# converter.net
KiCad netlist of a schematic drawn in Altium Designer
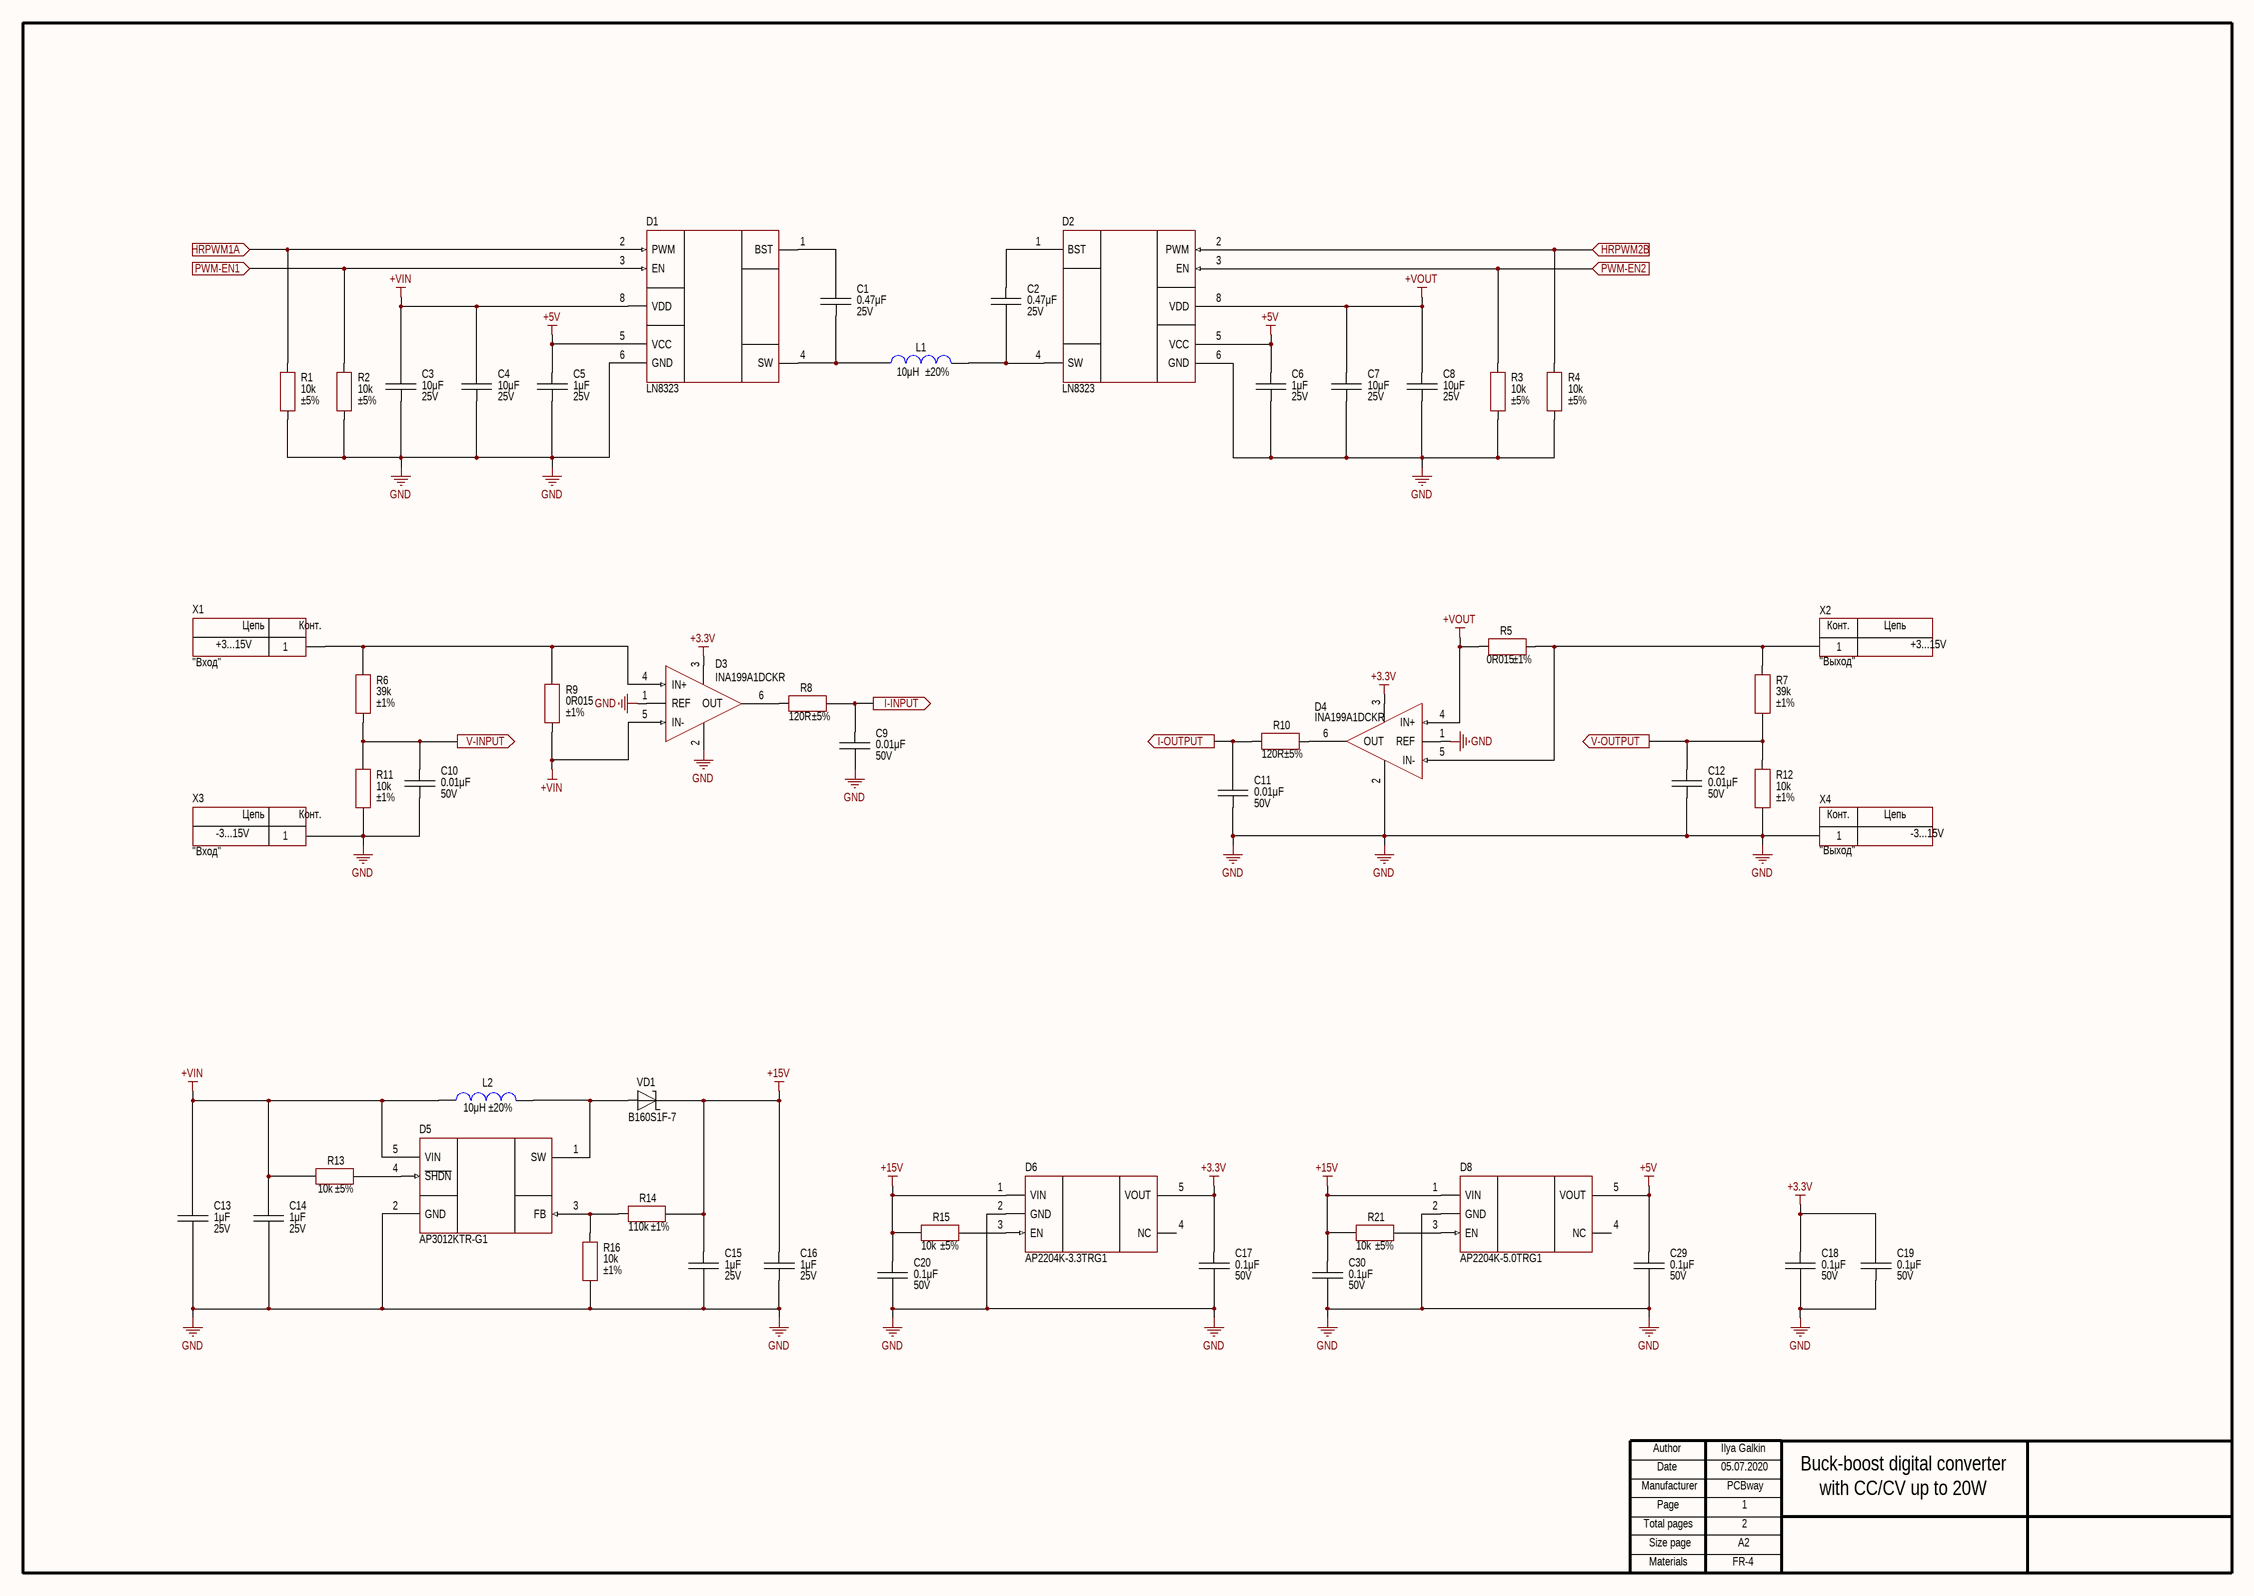
[diagram p0: converter.SchDoc]

(export (version "E")
  (design (tool "Eeschema 10.0.6"))
  (components
    (comp (ref "C1")
      (value "0.47μF")
      (footprint "CAP: 0805")
      (fields
        (field (name "MANUFACTURER") "Samsung")
        (field (name "PARTNUMBER") "CL21B474KAFNNNG")
        (field (name "VALUEMANUFACTURERPARTNUMBER") "Ceramic capacitor, 0.47μF, X7R, ±10%, 25V, 0805, -55...+125°C")
        (field (name "VOLTAGE") "25V")
      )
      (libsource (lib "Capacitor") (part "Ceramic_0805"))
    )
    (comp (ref "C2")
      (value "0.47μF")
      (footprint "CAP: 0805")
      (fields
        (field (name "MANUFACTURER") "Samsung")
        (field (name "PARTNUMBER") "CL21B474KAFNNNG")
        (field (name "VALUEMANUFACTURERPARTNUMBER") "Ceramic capacitor, 0.47μF, X7R, ±10%, 25V, 0805, -55...+125°C")
        (field (name "VOLTAGE") "25V")
      )
      (libsource (lib "Capacitor") (part "Ceramic_0805"))
    )
    (comp (ref "C3")
      (value "10μF")
      (footprint "CAP: 1210")
      (fields
        (field (name "MANUFACTURER") "Samsung")
        (field (name "PARTNUMBER") "CL32B106KAJNNNE")
        (field (name "VALUEMANUFACTURERPARTNUMBER") "Ceramic capacitor, 10μF, X7R, ±10%, 25V, 1210, -55...+125°C")
        (field (name "VOLTAGE") "25V")
      )
      (libsource (lib "Capacitor") (part "Ceramic_1210"))
    )
    (comp (ref "C4")
      (value "10μF")
      (footprint "CAP: 1210")
      (fields
        (field (name "MANUFACTURER") "Samsung")
        (field (name "PARTNUMBER") "CL32B106KAJNNNE")
        (field (name "VALUEMANUFACTURERPARTNUMBER") "Ceramic capacitor, 10μF, X7R, ±10%, 25V, 1210, -55...+125°C")
        (field (name "VOLTAGE") "25V")
      )
      (libsource (lib "Capacitor") (part "Ceramic_1210"))
    )
    (comp (ref "C5")
      (value "1μF")
      (footprint "CAP: 0603")
      (fields
        (field (name "MANUFACTURER") "Samsung")
        (field (name "PARTNUMBER") "CL10B105KA8NNNC")
        (field (name "VALUEMANUFACTURERPARTNUMBER") "Ceramic capacitor, 1μF, X7R, ±10%, 25V, 0603, -55...+125°C")
        (field (name "VOLTAGE") "25V")
      )
      (libsource (lib "Capacitor") (part "Ceramic_0603"))
    )
    (comp (ref "C6")
      (value "1μF")
      (footprint "CAP: 0603")
      (fields
        (field (name "MANUFACTURER") "Samsung")
        (field (name "PARTNUMBER") "CL10B105KA8NNNC")
        (field (name "VALUEMANUFACTURERPARTNUMBER") "Ceramic capacitor, 1μF, X7R, ±10%, 25V, 0603, -55...+125°C")
        (field (name "VOLTAGE") "25V")
      )
      (libsource (lib "Capacitor") (part "Ceramic_0603"))
    )
    (comp (ref "C7")
      (value "10μF")
      (footprint "CAP: 1210")
      (fields
        (field (name "MANUFACTURER") "Samsung")
        (field (name "PARTNUMBER") "CL32B106KAJNNNE")
        (field (name "VALUEMANUFACTURERPARTNUMBER") "Ceramic capacitor, 10μF, X7R, ±10%, 25V, 1210, -55...+125°C")
        (field (name "VOLTAGE") "25V")
      )
      (libsource (lib "Capacitor") (part "Ceramic_1210"))
    )
    (comp (ref "C8")
      (value "10μF")
      (footprint "CAP: 1210")
      (fields
        (field (name "MANUFACTURER") "Samsung")
        (field (name "PARTNUMBER") "CL32B106KAJNNNE")
        (field (name "VALUEMANUFACTURERPARTNUMBER") "Ceramic capacitor, 10μF, X7R, ±10%, 25V, 1210, -55...+125°C")
        (field (name "VOLTAGE") "25V")
      )
      (libsource (lib "Capacitor") (part "Ceramic_1210"))
    )
    (comp (ref "C9")
      (value "0.01μF")
      (footprint "CAP: 0603")
      (fields
        (field (name "MANUFACTURER") "Yageo")
        (field (name "PARTNUMBER") "CL10B103KB8NNNC")
        (field (name "VALUEMANUFACTURERPARTNUMBER") "Ceramic capacitor, 0.01μF, X7R, ±10%, 50V, 0603, -55...+125°C")
        (field (name "VOLTAGE") "50V")
      )
      (libsource (lib "Capacitor") (part "Ceramic_0603"))
    )
    (comp (ref "C10")
      (value "0.01μF")
      (footprint "CAP: 0603")
      (fields
        (field (name "MANUFACTURER") "Yageo")
        (field (name "PARTNUMBER") "CL10B103KB8NNNC")
        (field (name "VALUEMANUFACTURERPARTNUMBER") "Ceramic capacitor, 0.01μF, X7R, ±10%, 50V, 0603, -55...+125°C")
        (field (name "VOLTAGE") "50V")
      )
      (libsource (lib "Capacitor") (part "Ceramic_0603"))
    )
    (comp (ref "C11")
      (value "0.01μF")
      (footprint "CAP: 0603")
      (fields
        (field (name "MANUFACTURER") "Yageo")
        (field (name "PARTNUMBER") "CL10B103KB8NNNC")
        (field (name "VALUEMANUFACTURERPARTNUMBER") "Ceramic capacitor, 0.01μF, X7R, ±10%, 50V, 0603, -55...+125°C")
        (field (name "VOLTAGE") "50V")
      )
      (libsource (lib "Capacitor") (part "Ceramic_0603"))
    )
    (comp (ref "C12")
      (value "0.01μF")
      (footprint "CAP: 0603")
      (fields
        (field (name "MANUFACTURER") "Yageo")
        (field (name "PARTNUMBER") "CL10B103KB8NNNC")
        (field (name "VALUEMANUFACTURERPARTNUMBER") "Ceramic capacitor, 0.01μF, X7R, ±10%, 50V, 0603, -55...+125°C")
        (field (name "VOLTAGE") "50V")
      )
      (libsource (lib "Capacitor") (part "Ceramic_0603"))
    )
    (comp (ref "C13")
      (value "1μF")
      (footprint "CAP: 0603")
      (fields
        (field (name "MANUFACTURER") "Samsung")
        (field (name "PARTNUMBER") "CL10B105KA8NNNC")
        (field (name "VALUEMANUFACTURERPARTNUMBER") "Ceramic capacitor, 1μF, X7R, ±10%, 25V, 0603, -55...+125°C")
        (field (name "VOLTAGE") "25V")
      )
      (libsource (lib "Capacitor") (part "Ceramic_0603"))
    )
    (comp (ref "C14")
      (value "1μF")
      (footprint "CAP: 0603")
      (fields
        (field (name "MANUFACTURER") "Samsung")
        (field (name "PARTNUMBER") "CL10B105KA8NNNC")
        (field (name "VALUEMANUFACTURERPARTNUMBER") "Ceramic capacitor, 1μF, X7R, ±10%, 25V, 0603, -55...+125°C")
        (field (name "VOLTAGE") "25V")
      )
      (libsource (lib "Capacitor") (part "Ceramic_0603"))
    )
    (comp (ref "C15")
      (value "1μF")
      (footprint "CAP: 0603")
      (fields
        (field (name "MANUFACTURER") "Samsung")
        (field (name "PARTNUMBER") "CL10B105KA8NNNC")
        (field (name "VALUEMANUFACTURERPARTNUMBER") "Ceramic capacitor, 1μF, X7R, ±10%, 25V, 0603, -55...+125°C")
        (field (name "VOLTAGE") "25V")
      )
      (libsource (lib "Capacitor") (part "Ceramic_0603"))
    )
    (comp (ref "C16")
      (value "1μF")
      (footprint "CAP: 0603")
      (fields
        (field (name "MANUFACTURER") "Samsung")
        (field (name "PARTNUMBER") "CL10B105KA8NNNC")
        (field (name "VALUEMANUFACTURERPARTNUMBER") "Ceramic capacitor, 1μF, X7R, ±10%, 25V, 0603, -55...+125°C")
        (field (name "VOLTAGE") "25V")
      )
      (libsource (lib "Capacitor") (part "Ceramic_0603"))
    )
    (comp (ref "C17")
      (value "0.1μF")
      (footprint "CAP: 0603")
      (fields
        (field (name "MANUFACTURER") "Yageo")
        (field (name "PARTNUMBER") "CL10B104KB8WPND")
        (field (name "VALUEMANUFACTURERPARTNUMBER") "Ceramic capacitor, 0.1μF, X7R, ±10%, 50V, 0603, -55...+125°C")
        (field (name "VOLTAGE") "50V")
      )
      (libsource (lib "Capacitor") (part "Ceramic_0603"))
    )
    (comp (ref "C18")
      (value "0.1μF")
      (footprint "CAP: 0603")
      (fields
        (field (name "MANUFACTURER") "Yageo")
        (field (name "PARTNUMBER") "CL10B104KB8WPND")
        (field (name "VALUEMANUFACTURERPARTNUMBER") "Ceramic capacitor, 0.1μF, X7R, ±10%, 50V, 0603, -55...+125°C")
        (field (name "VOLTAGE") "50V")
      )
      (libsource (lib "Capacitor") (part "Ceramic_0603"))
    )
    (comp (ref "C19")
      (value "0.1μF")
      (footprint "CAP: 0603")
      (fields
        (field (name "MANUFACTURER") "Yageo")
        (field (name "PARTNUMBER") "CL10B104KB8WPND")
        (field (name "VALUEMANUFACTURERPARTNUMBER") "Ceramic capacitor, 0.1μF, X7R, ±10%, 50V, 0603, -55...+125°C")
        (field (name "VOLTAGE") "50V")
      )
      (libsource (lib "Capacitor") (part "Ceramic_0603"))
    )
    (comp (ref "C20")
      (value "0.1μF")
      (footprint "CAP: 0603")
      (fields
        (field (name "MANUFACTURER") "Yageo")
        (field (name "PARTNUMBER") "CL10B104KB8WPND")
        (field (name "VALUEMANUFACTURERPARTNUMBER") "Ceramic capacitor, 0.1μF, X7R, ±10%, 50V, 0603, -55...+125°C")
        (field (name "VOLTAGE") "50V")
      )
      (libsource (lib "Capacitor") (part "Ceramic_0603"))
    )
    (comp (ref "C29")
      (value "0.1μF")
      (footprint "CAP: 0603")
      (fields
        (field (name "MANUFACTURER") "Yageo")
        (field (name "PARTNUMBER") "CL10B104KB8WPND")
        (field (name "VALUEMANUFACTURERPARTNUMBER") "Ceramic capacitor, 0.1μF, X7R, ±10%, 50V, 0603, -55...+125°C")
        (field (name "VOLTAGE") "50V")
      )
      (libsource (lib "Capacitor") (part "Ceramic_0603"))
    )
    (comp (ref "C30")
      (value "0.1μF")
      (footprint "CAP: 0603")
      (fields
        (field (name "MANUFACTURER") "Yageo")
        (field (name "PARTNUMBER") "CL10B104KB8WPND")
        (field (name "VALUEMANUFACTURERPARTNUMBER") "Ceramic capacitor, 0.1μF, X7R, ±10%, 50V, 0603, -55...+125°C")
        (field (name "VOLTAGE") "50V")
      )
      (libsource (lib "Capacitor") (part "Ceramic_0603"))
    )
    (comp (ref "D1")
      (value "~")
      (footprint "8-SOIC-PAD")
      (description "Gate driver")
      (fields
        (field (name "MANUFACTURER") "Chipown")
        (field (name "VALUEMANUFACTURERPARTNUMBER") "Half-bridge module, 2N channel, 100kHz, 6A, supply 4...30V, -40...+125°C, 8-SOIC-PAD")
        (field (name "PARTNUMBER") "LN8323")
      )
      (libsource (lib "") (part "LN8323_1"))
    )
    (comp (ref "D2")
      (value "~")
      (footprint "8-SOIC-PAD")
      (description "Gate driver")
      (fields
        (field (name "MANUFACTURER") "Chipown")
        (field (name "VALUEMANUFACTURERPARTNUMBER") "Half-bridge module, 2N channel, 100kHz, 6A, supply 4...30V, -40...+125°C, 8-SOIC-PAD")
        (field (name "PARTNUMBER") "LN8323")
      )
      (libsource (lib "IC. Gate driver") (part "LN8323"))
    )
    (comp (ref "D3")
      (value "~")
      (footprint "SC70-6")
      (description "Current monitor")
      (fields
        (field (name "MANUFACTURER") "Texas Instruments")
        (field (name "VALUEMANUFACTURERPARTNUMBER") "IC current monitor, ±1.5%, 50V/V, -0.3...+26V, -40...+125°C, SOT23-5")
        (field (name "PARTNUMBER") "INA199A1DCKR")
      )
      (libsource (lib "IC. Sensor") (part "INA199A1DCKR"))
    )
    (comp (ref "D4")
      (value "~")
      (footprint "SC70-6")
      (description "Current monitor")
      (fields
        (field (name "MANUFACTURER") "Texas Instruments")
        (field (name "VALUEMANUFACTURERPARTNUMBER") "IC current monitor, ±1.5%, 50V/V, -0.3...+26V, -40...+125°C, SOT23-5")
        (field (name "PARTNUMBER") "INA199A1DCKR")
      )
      (libsource (lib "IC. Sensor") (part "INA199A1DCKR"))
    )
    (comp (ref "D5")
      (value "~")
      (footprint "SOT23-5")
      (description "Boost converter")
      (fields
        (field (name "MANUFACTURER") "Diodes Incorporated")
        (field (name "VALUEMANUFACTURERPARTNUMBER") "DC/DC boost converter, input 2.6...16V, 1.5MHz, output 3...29V, 0.5A, -40...+85°C, SOT23-5")
        (field (name "PARTNUMBER") "AP3012KTR-G1")
      )
      (libsource (lib "IC. Power supply") (part "AP3012KTR-G1"))
    )
    (comp (ref "D6")
      (value "~")
      (footprint "SOT23-5")
      (description "Linear voltage regulator")
      (fields
        (field (name "MANUFACTURER") "Diodes Incorporated")
        (field (name "VALUEMANUFACTURERPARTNUMBER") "Linear voltage regulator, input 4...24V, 0.5V, output 3.3V, 0.15A, -40...+85°C, SOT23-6")
        (field (name "PARTNUMBER") "AP2204K-3.3TRG1")
      )
      (libsource (lib "IC. Power supply") (part "AP2204K-3.3TRG1"))
    )
    (comp (ref "D8")
      (value "~")
      (footprint "SOT23-5")
      (description "Linear voltage regulator")
      (fields
        (field (name "MANUFACTURER") "Diodes Incorporated")
        (field (name "VALUEMANUFACTURERPARTNUMBER") "Linear voltage regulator, input 4...24V, 0.5V, output 5V, 0.15A, -40...+85°C, SOT23-6")
        (field (name "PARTNUMBER") "AP2204K-5.0TRG1")
      )
      (libsource (lib "IC. Power supply") (part "AP2204K-3.3TRG1"))
    )
    (comp (ref "L1")
      (value "10μH")
      (footprint "IND: SDR1006")
      (fields
        (field (name "MANUFACTURER") "Bourns")
        (field (name "PARTNUMBER") "SDR1006-100ML")
        (field (name "VALUEMANUFACTURERPARTNUMBER") "Fixed inductor, 10μH, ±20%, SDR0805, 2.6A, -40...+125°C")
        (field (name "TOLERANCE") "±20%")
      )
      (libsource (lib "Inductor") (part "Inductor_SDR1006"))
    )
    (comp (ref "L2")
      (value "10μH")
      (footprint "IND: SDR0403")
      (fields
        (field (name "MANUFACTURER") "Bourns")
        (field (name "PARTNUMBER") "SDR0403-100ML")
        (field (name "VALUEMANUFACTURERPARTNUMBER") "Fixed inductor, 10μH, ±20%, SDR0403, 1.15A, -40...+125°C")
        (field (name "TOLERANCE") "±20%")
      )
      (libsource (lib "Inductor") (part "Inductor_SDR0403"))
    )
    (comp (ref "R1")
      (value "10k")
      (footprint "RES: 0603")
      (fields
        (field (name "MANUFACTURER") "Yageo")
        (field (name "PARTNUMBER") "RC0603JR-0710KL")
        (field (name "VALUEMANUFACTURERPARTNUMBER") "Resistor film, 10k, ±5%, 0603, 0.1W, -55...+125°C")
        (field (name "TOLERANCE") "±5%")
      )
      (libsource (lib "Resistor") (part "Resistor_0603"))
    )
    (comp (ref "R2")
      (value "10k")
      (footprint "RES: 0603")
      (fields
        (field (name "MANUFACTURER") "Yageo")
        (field (name "PARTNUMBER") "RC0603JR-0710KL")
        (field (name "VALUEMANUFACTURERPARTNUMBER") "Resistor film, 10k, ±5%, 0603, 0.1W, -55...+125°C")
        (field (name "TOLERANCE") "±5%")
      )
      (libsource (lib "Resistor") (part "Resistor_0603"))
    )
    (comp (ref "R3")
      (value "10k")
      (footprint "RES: 0603")
      (fields
        (field (name "MANUFACTURER") "Yageo")
        (field (name "PARTNUMBER") "RC0603JR-0710KL")
        (field (name "VALUEMANUFACTURERPARTNUMBER") "Resistor film, 10k, ±5%, 0603, 0.1W, -55...+125°C")
        (field (name "TOLERANCE") "±5%")
      )
      (libsource (lib "Resistor") (part "Resistor_0603"))
    )
    (comp (ref "R4")
      (value "10k")
      (footprint "RES: 0603")
      (fields
        (field (name "MANUFACTURER") "Yageo")
        (field (name "PARTNUMBER") "RC0603JR-0710KL")
        (field (name "VALUEMANUFACTURERPARTNUMBER") "Resistor film, 10k, ±5%, 0603, 0.1W, -55...+125°C")
        (field (name "TOLERANCE") "±5%")
      )
      (libsource (lib "Resistor") (part "Resistor_0603"))
    )
    (comp (ref "R5")
      (value "0R015")
      (footprint "RES: CSS2H (2512)")
      (fields
        (field (name "MANUFACTURER") "Yageo")
        (field (name "PARTNUMBER") "PE2512FKE7W0R015L")
        (field (name "VALUEMANUFACTURERPARTNUMBER") "Resistor film, 0R015, ±1%, 2512, 2W, -55...+170°C")
        (field (name "TOLERANCE") "±1%")
      )
      (libsource (lib "Resistor") (part "Shunt"))
    )
    (comp (ref "R6")
      (value "39k")
      (footprint "RES: 0603")
      (fields
        (field (name "MANUFACTURER") "Yageo")
        (field (name "PARTNUMBER") "RC0603FR-0739KL")
        (field (name "VALUEMANUFACTURERPARTNUMBER") "Resistor film, 39k, ±1%, 0603, 0.1W, -55...+125°C")
        (field (name "TOLERANCE") "±1%")
      )
      (libsource (lib "Resistor") (part "Resistor_0603"))
    )
    (comp (ref "R7")
      (value "39k")
      (footprint "RES: 0603")
      (fields
        (field (name "MANUFACTURER") "Yageo")
        (field (name "PARTNUMBER") "RC0603FR-0739KL")
        (field (name "VALUEMANUFACTURERPARTNUMBER") "Resistor film, 39k, ±1%, 0603, 0.1W, -55...+125°C")
        (field (name "TOLERANCE") "±1%")
      )
      (libsource (lib "Resistor") (part "Resistor_0603"))
    )
    (comp (ref "R8")
      (value "120R")
      (footprint "RES: 0603")
      (fields
        (field (name "MANUFACTURER") "Yageo")
        (field (name "PARTNUMBER") "RC0603JR-07120RL")
        (field (name "VALUEMANUFACTURERPARTNUMBER") "Resistor film, 120R, ±5%, 0603, 0.1W, -55...+125°C")
        (field (name "TOLERANCE") "±5%")
      )
      (libsource (lib "") (part "Resistor_0603_2"))
    )
    (comp (ref "R9")
      (value "0R015")
      (footprint "RES: CSS2H (2512)")
      (fields
        (field (name "MANUFACTURER") "Yageo")
        (field (name "PARTNUMBER") "PE2512FKE7W0R015L")
        (field (name "VALUEMANUFACTURERPARTNUMBER") "Resistor film, 0R015, ±1%, 2512, 2W, -55...+170°C")
        (field (name "TOLERANCE") "±1%")
      )
      (libsource (lib "") (part "Shunt_1"))
    )
    (comp (ref "R10")
      (value "120R")
      (footprint "RES: 0603")
      (fields
        (field (name "MANUFACTURER") "Yageo")
        (field (name "PARTNUMBER") "RC0603JR-07120RL")
        (field (name "VALUEMANUFACTURERPARTNUMBER") "Resistor film, 120R, ±5%, 0603, 0.1W, -55...+125°C")
        (field (name "TOLERANCE") "±5%")
      )
      (libsource (lib "") (part "Resistor_0603_2"))
    )
    (comp (ref "R11")
      (value "10k")
      (footprint "RES: 0603")
      (fields
        (field (name "MANUFACTURER") "Yageo")
        (field (name "PARTNUMBER") "RC0603FR-0710KL")
        (field (name "VALUEMANUFACTURERPARTNUMBER") "Resistor film, 10k, ±1%, 0603, 0.1W, -55...+125°C")
        (field (name "TOLERANCE") "±1%")
      )
      (libsource (lib "Resistor") (part "Resistor_0603"))
    )
    (comp (ref "R12")
      (value "10k")
      (footprint "RES: 0603")
      (fields
        (field (name "MANUFACTURER") "Yageo")
        (field (name "PARTNUMBER") "RC0603FR-0710KL")
        (field (name "VALUEMANUFACTURERPARTNUMBER") "Resistor film, 10k, ±1%, 0603, 0.1W, -55...+125°C")
        (field (name "TOLERANCE") "±1%")
      )
      (libsource (lib "Resistor") (part "Resistor_0603"))
    )
    (comp (ref "R13")
      (value "10k")
      (footprint "RES: 0603")
      (fields
        (field (name "MANUFACTURER") "Yageo")
        (field (name "PARTNUMBER") "RC0603JR-0710KL")
        (field (name "VALUEMANUFACTURERPARTNUMBER") "Resistor film, 10k, ±5%, 0603, 0.1W, -55...+125°C")
        (field (name "TOLERANCE") "±5%")
      )
      (libsource (lib "") (part "Resistor_0603_1"))
    )
    (comp (ref "R14")
      (value "110k")
      (footprint "RES: 0603")
      (fields
        (field (name "MANUFACTURER") "Yageo")
        (field (name "PARTNUMBER") "RC0603FR-07110KL")
        (field (name "VALUEMANUFACTURERPARTNUMBER") "Resistor film, 110k, ±1%, 0603, 0.1W, -55...+125°C")
        (field (name "TOLERANCE") "±1%")
      )
      (libsource (lib "") (part "Resistor_0603_1"))
    )
    (comp (ref "R15")
      (value "10k")
      (footprint "RES: 0603")
      (fields
        (field (name "MANUFACTURER") "Yageo")
        (field (name "PARTNUMBER") "RC0603JR-0710KL")
        (field (name "VALUEMANUFACTURERPARTNUMBER") "Resistor film, 10k, ±5%, 0603, 0.1W, -55...+125°C")
        (field (name "TOLERANCE") "±5%")
      )
      (libsource (lib "") (part "Resistor_0603_1"))
    )
    (comp (ref "R16")
      (value "10k")
      (footprint "RES: 0603")
      (fields
        (field (name "MANUFACTURER") "Yageo")
        (field (name "PARTNUMBER") "RC0603FR-0710KL")
        (field (name "VALUEMANUFACTURERPARTNUMBER") "Resistor film, 10k, ±1%, 0603, 0.1W, -55...+125°C")
        (field (name "TOLERANCE") "±1%")
      )
      (libsource (lib "Resistor") (part "Resistor_0603"))
    )
    (comp (ref "R21")
      (value "10k")
      (footprint "RES: 0603")
      (fields
        (field (name "MANUFACTURER") "Yageo")
        (field (name "PARTNUMBER") "RC0603JR-0710KL")
        (field (name "VALUEMANUFACTURERPARTNUMBER") "Resistor film, 10k, ±5%, 0603, 0.1W, -55...+125°C")
        (field (name "TOLERANCE") "±5%")
      )
      (libsource (lib "") (part "Resistor_0603_1"))
    )
    (comp (ref "VD1")
      (value "~")
      (footprint "DIODE: SOD123F")
      (fields
        (field (name "MANUFACTURER") "Diodes Incorporated")
        (field (name "VALUEMANUFACTURERPARTNUMBER") "Schottky diode, 60B160S1F-7, 1A, 650mV, 45pF, SOD-123F, -55...+150°C")
        (field (name "VOLTAGE") "60B160S1F-7")
        (field (name "PARTNUMBER") "B160S1F-7")
      )
      (libsource (lib "Diode") (part "Schottky_single"))
    )
    (comp (ref "X1")
      (value "~")
      (footprint "CON: 8191")
      (fields
        (field (name "MANUFACTURER") "Keystone")
        (field (name "VALUEMANUFACTURERPARTNUMBER") "Power connector, 500V, 15A")
        (field (name "PARTNUMBER") "8191")
        (field (name "COMMENTTEXT") "\"Вход\"")
      )
      (libsource (lib "Connector") (part "Connector_single_power"))
    )
    (comp (ref "X2")
      (value "~")
      (footprint "CON: 8191")
      (fields
        (field (name "MANUFACTURER") "Keystone")
        (field (name "VALUEMANUFACTURERPARTNUMBER") "Power connector, 500V, 15A")
        (field (name "PARTNUMBER") "8191")
        (field (name "COMMENTTEXT") "\"Выход\"")
      )
      (libsource (lib "") (part "Connector_single_power_1"))
    )
    (comp (ref "X3")
      (value "~")
      (footprint "CON: 8191")
      (fields
        (field (name "MANUFACTURER") "Keystone")
        (field (name "VALUEMANUFACTURERPARTNUMBER") "Power connector, 500V, 15A")
        (field (name "PARTNUMBER") "8191")
        (field (name "COMMENTTEXT") "\"Вход\"")
      )
      (libsource (lib "Connector") (part "Connector_single_power"))
    )
    (comp (ref "X4")
      (value "~")
      (footprint "CON: 8191")
      (fields
        (field (name "MANUFACTURER") "Keystone")
        (field (name "VALUEMANUFACTURERPARTNUMBER") "Power connector, 500V, 15A")
        (field (name "PARTNUMBER") "8191")
        (field (name "COMMENTTEXT") "\"Выход\"")
      )
      (libsource (lib "") (part "Connector_single_power_1"))
    )
  )
  (nets
    (net (code "1") (name "+3.3V") (class "Default")
      (node (ref "C17") (pin "2") (pinfunction "2_2") (pintype "power_in"))
      (node (ref "C18") (pin "2") (pinfunction "2_2") (pintype "power_in"))
      (node (ref "C19") (pin "2") (pinfunction "2_2") (pintype "power_in"))
      (node (ref "D3") (pin "3") (pinfunction "V+_3") (pintype "power_in"))
      (node (ref "D4") (pin "3") (pinfunction "V+_3") (pintype "power_in"))
      (node (ref "D6") (pin "5") (pinfunction "VOUT_5") (pintype "passive"))
    )
    (net (code "2") (name "+5V") (class "Default")
      (node (ref "C29") (pin "2") (pinfunction "2_2") (pintype "power_in"))
      (node (ref "C5") (pin "2") (pinfunction "2_2") (pintype "power_in"))
      (node (ref "C6") (pin "2") (pinfunction "2_2") (pintype "power_in"))
      (node (ref "D1") (pin "5") (pinfunction "VCC_5") (pintype "passive"))
      (node (ref "D2") (pin "5") (pinfunction "VCC_5") (pintype "passive"))
      (node (ref "D8") (pin "5") (pinfunction "VOUT_5") (pintype "passive"))
    )
    (net (code "3") (name "+15V") (class "Default")
      (node (ref "C15") (pin "2") (pinfunction "2_2") (pintype "power_in"))
      (node (ref "C16") (pin "2") (pinfunction "2_2") (pintype "power_in"))
      (node (ref "C20") (pin "2") (pinfunction "2_2") (pintype "power_in"))
      (node (ref "C30") (pin "2") (pinfunction "2_2") (pintype "power_in"))
      (node (ref "D6") (pin "1") (pinfunction "VIN_1") (pintype "passive"))
      (node (ref "D8") (pin "1") (pinfunction "VIN_1") (pintype "passive"))
      (node (ref "R14") (pin "1") (pinfunction "1_1") (pintype "passive"))
      (node (ref "R15") (pin "2") (pinfunction "2_2") (pintype "passive"))
      (node (ref "R21") (pin "2") (pinfunction "2_2") (pintype "passive"))
      (node (ref "VD1") (pin "2") (pinfunction "2_2") (pintype "passive"))
    )
    (net (code "4") (name "+VIN") (class "Default")
      (node (ref "C13") (pin "2") (pinfunction "2_2") (pintype "power_in"))
      (node (ref "C14") (pin "2") (pinfunction "2_2") (pintype "power_in"))
      (node (ref "C3") (pin "2") (pinfunction "2_2") (pintype "power_in"))
      (node (ref "C4") (pin "2") (pinfunction "2_2") (pintype "power_in"))
      (node (ref "D1") (pin "8") (pinfunction "VDD_8") (pintype "passive"))
      (node (ref "D3") (pin "5") (pinfunction "IN-_5") (pintype "input"))
      (node (ref "D5") (pin "5") (pinfunction "VIN_5") (pintype "passive"))
      (node (ref "L2") (pin "2") (pinfunction "2_2") (pintype "passive"))
      (node (ref "R13") (pin "2") (pinfunction "2_2") (pintype "passive"))
      (node (ref "R9") (pin "2") (pinfunction "2_2") (pintype "passive"))
    )
    (net (code "5") (name "+VOUT") (class "Default")
      (node (ref "C7") (pin "2") (pinfunction "2_2") (pintype "power_in"))
      (node (ref "C8") (pin "2") (pinfunction "2_2") (pintype "power_in"))
      (node (ref "D2") (pin "8") (pinfunction "VDD_8") (pintype "passive"))
      (node (ref "D4") (pin "4") (pinfunction "IN+_4") (pintype "input"))
      (node (ref "R5") (pin "1") (pinfunction "1_1") (pintype "passive"))
    )
    (net (code "6") (name "/HRPWM1A") (class "Default")
      (node (ref "D1") (pin "2") (pinfunction "PWM_2") (pintype "input"))
      (node (ref "R1") (pin "2") (pinfunction "2_2") (pintype "passive"))
    )
    (net (code "7") (name "/HRPWM2B") (class "Default")
      (node (ref "D2") (pin "2") (pinfunction "PWM_2") (pintype "input"))
      (node (ref "R4") (pin "2") (pinfunction "2_2") (pintype "passive"))
    )
    (net (code "8") (name "/I-INPUT") (class "Default")
      (node (ref "C9") (pin "2") (pinfunction "2_2") (pintype "power_in"))
      (node (ref "R8") (pin "2") (pinfunction "2_2") (pintype "passive"))
    )
    (net (code "9") (name "/I-OUTPUT") (class "Default")
      (node (ref "C11") (pin "2") (pinfunction "2_2") (pintype "power_in"))
      (node (ref "R10") (pin "1") (pinfunction "1_1") (pintype "passive"))
    )
    (net (code "10") (name "/PWM-EN1") (class "Default")
      (node (ref "D1") (pin "3") (pinfunction "EN_3") (pintype "input"))
      (node (ref "R2") (pin "2") (pinfunction "2_2") (pintype "passive"))
    )
    (net (code "11") (name "/PWM-EN2") (class "Default")
      (node (ref "D2") (pin "3") (pinfunction "EN_3") (pintype "input"))
      (node (ref "R3") (pin "2") (pinfunction "2_2") (pintype "passive"))
    )
    (net (code "12") (name "/V-INPUT") (class "Default")
      (node (ref "C10") (pin "2") (pinfunction "2_2") (pintype "power_in"))
      (node (ref "R11") (pin "2") (pinfunction "2_2") (pintype "passive"))
      (node (ref "R6") (pin "1") (pinfunction "1_1") (pintype "passive"))
    )
    (net (code "13") (name "/V-OUTPUT") (class "Default")
      (node (ref "C12") (pin "2") (pinfunction "2_2") (pintype "power_in"))
      (node (ref "R12") (pin "2") (pinfunction "2_2") (pintype "passive"))
      (node (ref "R7") (pin "1") (pinfunction "1_1") (pintype "passive"))
    )
    (net (code "14") (name "GND") (class "Default")
      (node (ref "C10") (pin "1") (pinfunction "1_1") (pintype "power_in"))
      (node (ref "C11") (pin "1") (pinfunction "1_1") (pintype "power_in"))
      (node (ref "C12") (pin "1") (pinfunction "1_1") (pintype "power_in"))
      (node (ref "C13") (pin "1") (pinfunction "1_1") (pintype "power_in"))
      (node (ref "C14") (pin "1") (pinfunction "1_1") (pintype "power_in"))
      (node (ref "C15") (pin "1") (pinfunction "1_1") (pintype "power_in"))
      (node (ref "C16") (pin "1") (pinfunction "1_1") (pintype "power_in"))
      (node (ref "C17") (pin "1") (pinfunction "1_1") (pintype "power_in"))
      (node (ref "C18") (pin "1") (pinfunction "1_1") (pintype "power_in"))
      (node (ref "C19") (pin "1") (pinfunction "1_1") (pintype "power_in"))
      (node (ref "C20") (pin "1") (pinfunction "1_1") (pintype "power_in"))
      (node (ref "C29") (pin "1") (pinfunction "1_1") (pintype "power_in"))
      (node (ref "C3") (pin "1") (pinfunction "1_1") (pintype "power_in"))
      (node (ref "C30") (pin "1") (pinfunction "1_1") (pintype "power_in"))
      (node (ref "C4") (pin "1") (pinfunction "1_1") (pintype "power_in"))
      (node (ref "C5") (pin "1") (pinfunction "1_1") (pintype "power_in"))
      (node (ref "C6") (pin "1") (pinfunction "1_1") (pintype "power_in"))
      (node (ref "C7") (pin "1") (pinfunction "1_1") (pintype "power_in"))
      (node (ref "C8") (pin "1") (pinfunction "1_1") (pintype "power_in"))
      (node (ref "C9") (pin "1") (pinfunction "1_1") (pintype "power_in"))
      (node (ref "D1") (pin "6") (pinfunction "GND_6") (pintype "passive"))
      (node (ref "D2") (pin "6") (pinfunction "GND_6") (pintype "passive"))
      (node (ref "D3") (pin "1") (pinfunction "REF_1") (pintype "power_in"))
      (node (ref "D3") (pin "2") (pinfunction "V-_2") (pintype "power_in"))
      (node (ref "D4") (pin "1") (pinfunction "REF_1") (pintype "power_in"))
      (node (ref "D4") (pin "2") (pinfunction "V-_2") (pintype "power_in"))
      (node (ref "D5") (pin "2") (pinfunction "GND_2") (pintype "passive"))
      (node (ref "D6") (pin "2") (pinfunction "GND_2") (pintype "passive"))
      (node (ref "D8") (pin "2") (pinfunction "GND_2") (pintype "passive"))
      (node (ref "R1") (pin "1") (pinfunction "1_1") (pintype "passive"))
      (node (ref "R11") (pin "1") (pinfunction "1_1") (pintype "passive"))
      (node (ref "R12") (pin "1") (pinfunction "1_1") (pintype "passive"))
      (node (ref "R16") (pin "1") (pinfunction "1_1") (pintype "passive"))
      (node (ref "R2") (pin "1") (pinfunction "1_1") (pintype "passive"))
      (node (ref "R3") (pin "1") (pinfunction "1_1") (pintype "passive"))
      (node (ref "R4") (pin "1") (pinfunction "1_1") (pintype "passive"))
      (node (ref "X3") (pin "1") (pinfunction "1_1") (pintype "passive"))
      (node (ref "X4") (pin "1") (pinfunction "1_1") (pintype "passive"))
    )
    (net (code "15") (name "Net-(D1-BST)") (class "Default")
      (node (ref "C1") (pin "2") (pinfunction "2_2") (pintype "power_in"))
      (node (ref "D1") (pin "1") (pinfunction "BST_1") (pintype "passive"))
    )
    (net (code "16") (name "Net-(D1-SW)") (class "Default")
      (node (ref "C1") (pin "1") (pinfunction "1_1") (pintype "power_in"))
      (node (ref "D1") (pin "4") (pinfunction "SW_4") (pintype "passive"))
      (node (ref "L1") (pin "2") (pinfunction "2_2") (pintype "passive"))
    )
    (net (code "17") (name "Net-(D2-BST)") (class "Default")
      (node (ref "C2") (pin "2") (pinfunction "2_2") (pintype "power_in"))
      (node (ref "D2") (pin "1") (pinfunction "BST_1") (pintype "passive"))
    )
    (net (code "18") (name "Net-(D2-SW)") (class "Default")
      (node (ref "C2") (pin "1") (pinfunction "1_1") (pintype "power_in"))
      (node (ref "D2") (pin "4") (pinfunction "SW_4") (pintype "passive"))
      (node (ref "L1") (pin "1") (pinfunction "1_1") (pintype "passive"))
    )
    (net (code "19") (name "Net-(D3-IN+)") (class "Default")
      (node (ref "D3") (pin "4") (pinfunction "IN+_4") (pintype "input"))
      (node (ref "R6") (pin "2") (pinfunction "2_2") (pintype "passive"))
      (node (ref "R9") (pin "1") (pinfunction "1_1") (pintype "passive"))
      (node (ref "X1") (pin "1") (pinfunction "1_1") (pintype "passive"))
    )
    (net (code "20") (name "Net-(D3-OUT)") (class "Default")
      (node (ref "D3") (pin "6") (pinfunction "OUT_6") (pintype "power_in"))
      (node (ref "R8") (pin "1") (pinfunction "1_1") (pintype "passive"))
    )
    (net (code "21") (name "Net-(D4-IN-)") (class "Default")
      (node (ref "D4") (pin "5") (pinfunction "IN-_5") (pintype "input"))
      (node (ref "R5") (pin "2") (pinfunction "2_2") (pintype "passive"))
      (node (ref "R7") (pin "2") (pinfunction "2_2") (pintype "passive"))
      (node (ref "X2") (pin "1") (pinfunction "1_1") (pintype "passive"))
    )
    (net (code "22") (name "Net-(D4-OUT)") (class "Default")
      (node (ref "D4") (pin "6") (pinfunction "OUT_6") (pintype "power_in"))
      (node (ref "R10") (pin "2") (pinfunction "2_2") (pintype "passive"))
    )
    (net (code "23") (name "Net-(D5-FB)") (class "Default")
      (node (ref "D5") (pin "3") (pinfunction "FB_3") (pintype "input"))
      (node (ref "R14") (pin "2") (pinfunction "2_2") (pintype "passive"))
      (node (ref "R16") (pin "2") (pinfunction "2_2") (pintype "passive"))
    )
    (net (code "24") (name "Net-(D5-SW)") (class "Default")
      (node (ref "D5") (pin "1") (pinfunction "SW_1") (pintype "passive"))
      (node (ref "L2") (pin "1") (pinfunction "1_1") (pintype "passive"))
      (node (ref "VD1") (pin "1") (pinfunction "1_1") (pintype "passive"))
    )
    (net (code "25") (name "Net-(D5-~{SHDN})") (class "Default")
      (node (ref "D5") (pin "4") (pinfunction "~{SHDN}_4") (pintype "input"))
      (node (ref "R13") (pin "1") (pinfunction "1_1") (pintype "passive"))
    )
    (net (code "26") (name "Net-(D6-EN)") (class "Default")
      (node (ref "D6") (pin "3") (pinfunction "EN_3") (pintype "input"))
      (node (ref "R15") (pin "1") (pinfunction "1_1") (pintype "passive"))
    )
    (net (code "27") (name "Net-(D8-EN)") (class "Default")
      (node (ref "D8") (pin "3") (pinfunction "EN_3") (pintype "input"))
      (node (ref "R21") (pin "1") (pinfunction "1_1") (pintype "passive"))
    )
    (net (code "28") (name "unconnected-(D6-NC-Pad4)") (class "Default")
      (node (ref "D6") (pin "4") (pinfunction "NC_4") (pintype "passive"))
    )
    (net (code "29") (name "unconnected-(D8-NC-Pad4)") (class "Default")
      (node (ref "D8") (pin "4") (pinfunction "NC_4") (pintype "passive"))
    )
  )
)
